# AI_XiaoZhi_WIFI.net
KiCad netlist of a schematic drawn in Altium Designer
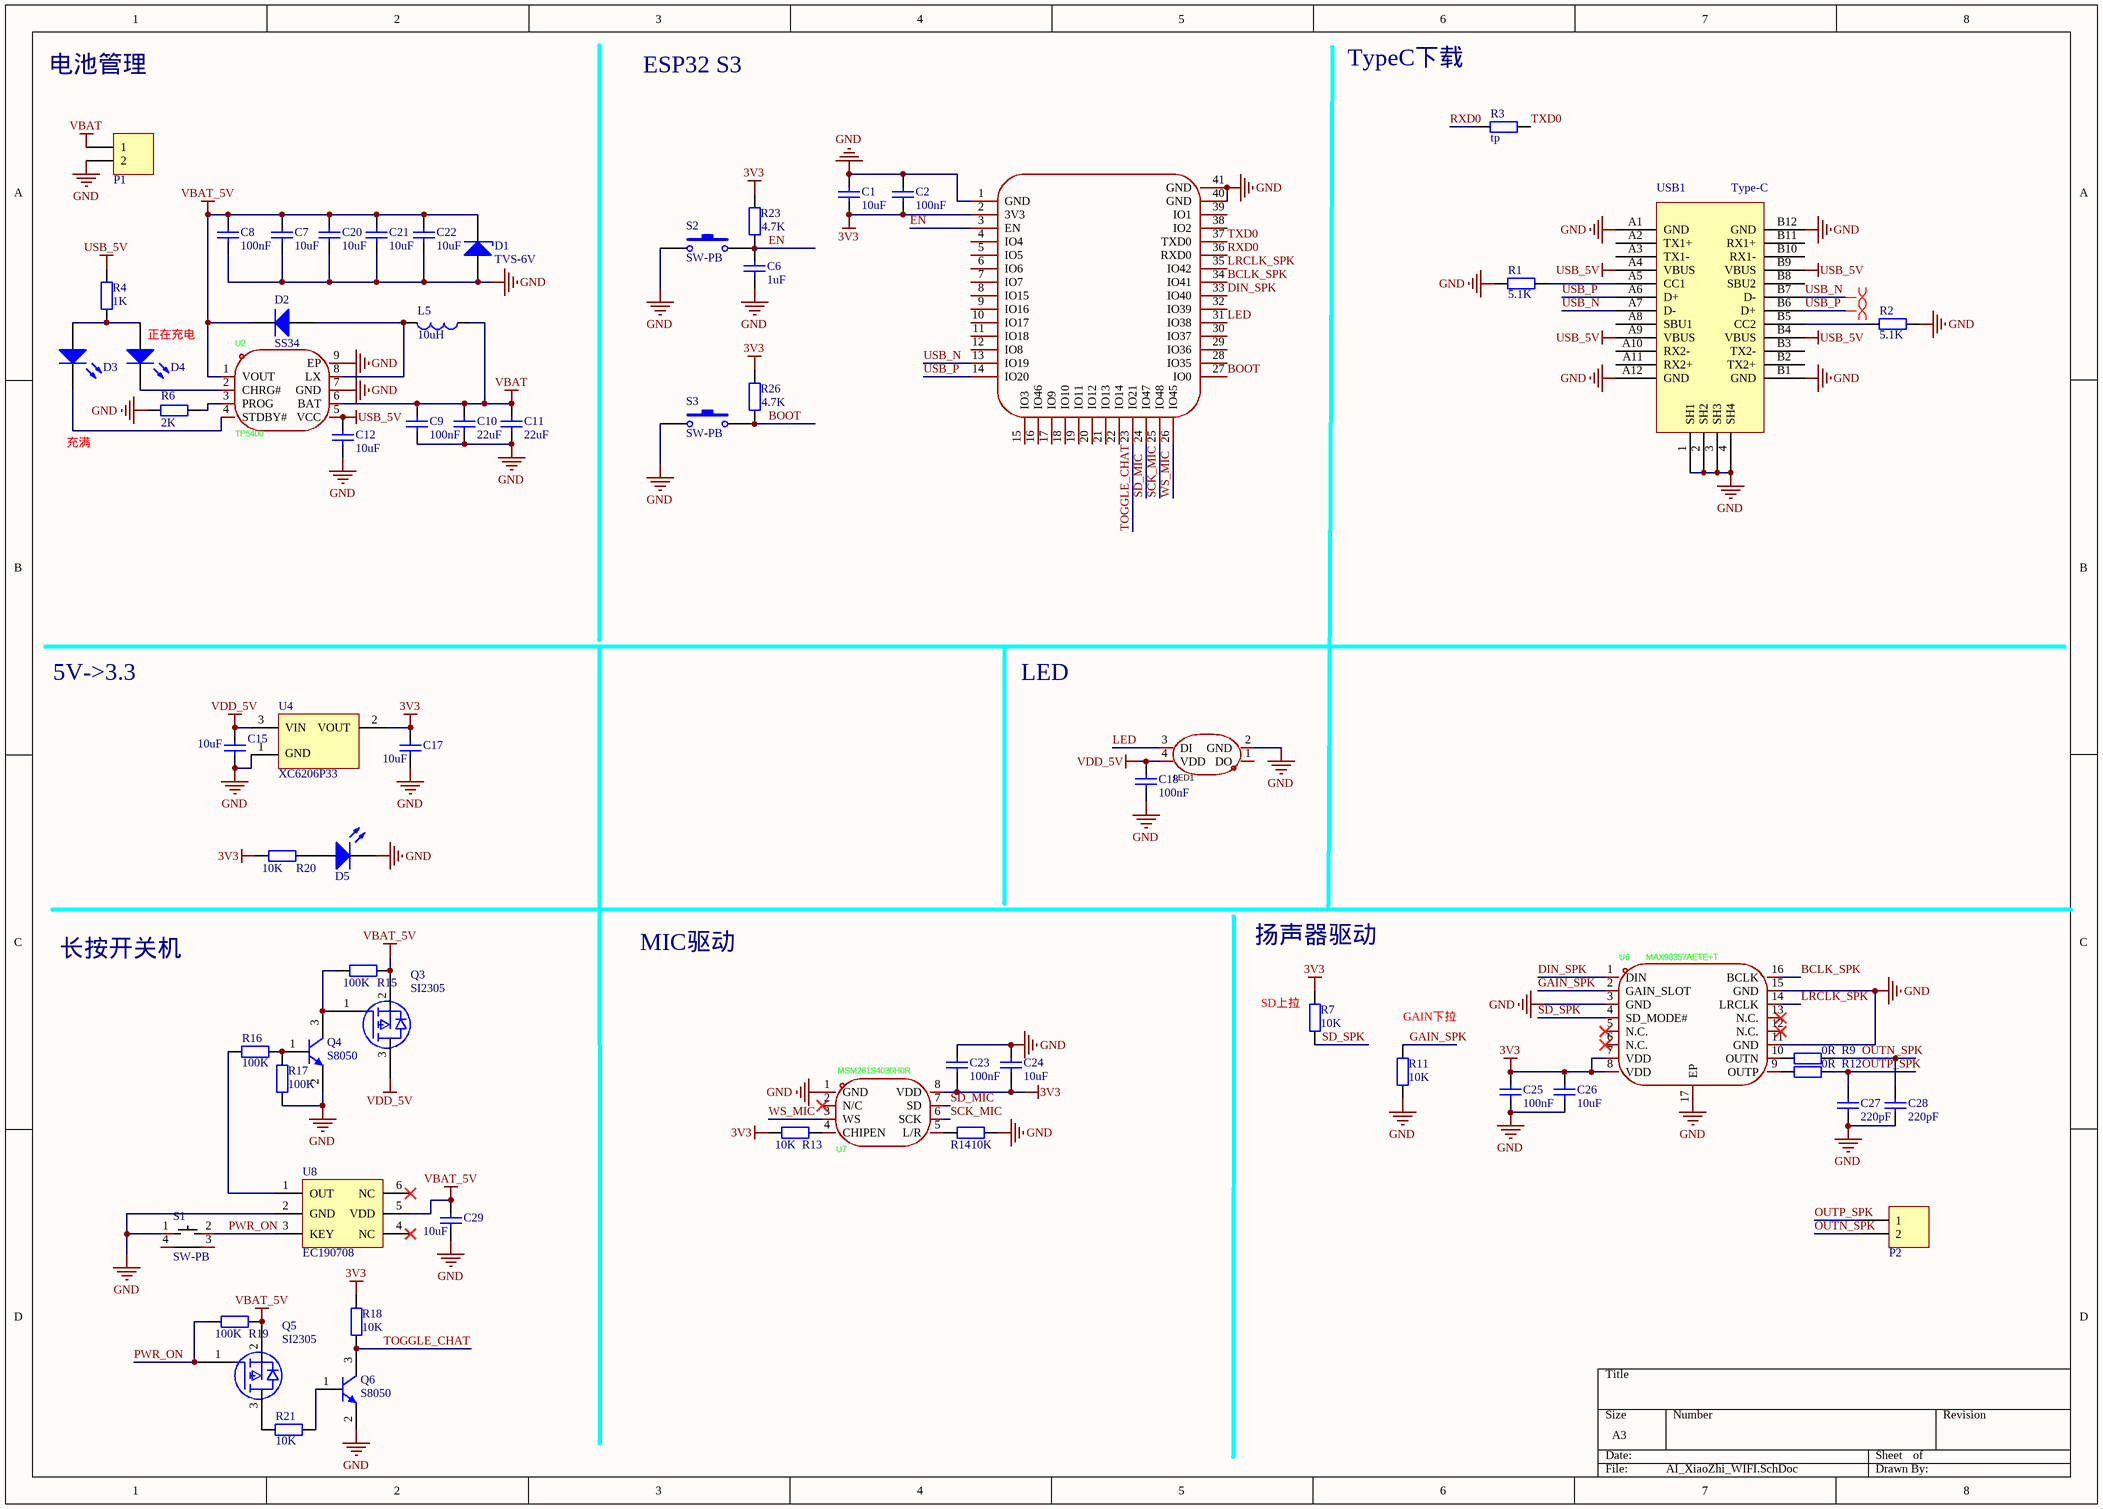
[diagram p0: AI_XiaoZhi_WIFI.SchDoc]

(export (version "E")
  (design (tool "Eeschema 10.0.6"))
  (components
    (comp (ref "C1")
      (value "10uF")
      (footprint "PCBPcblib_MXJ:0603-C")
      (description "无极性电容")
      (fields (field (name "Comment") "CAP") (field (name "PUBLISHER") "Altium Limited"))
      (libsource (lib "PCBSchlib_MXJ") (part "CAP"))
    )
    (comp (ref "C2")
      (value "100nF")
      (footprint "PCBPcblib_MXJ:0603-C")
      (description "无极性电容")
      (fields (field (name "Comment") "CAP") (field (name "PUBLISHER") "Altium Limited"))
      (libsource (lib "PCBSchlib_MXJ") (part "CAP"))
    )
    (comp (ref "C6")
      (value "1uF")
      (footprint "PCBPcblib_MXJ:0603-C")
      (description "无极性电容")
      (fields (field (name "Comment") "CAP") (field (name "PUBLISHER") "Altium Limited"))
      (libsource (lib "PCBSchlib_MXJ") (part "CAP"))
    )
    (comp (ref "C7")
      (value "10uF")
      (footprint "PCBPcblib_MXJ:0603-C")
      (description "无极性电容")
      (fields (field (name "Comment") "CAP") (field (name "PUBLISHER") "Altium Limited"))
      (libsource (lib "PCBSchlib_MXJ") (part "CAP"))
    )
    (comp (ref "C8")
      (value "100nF")
      (footprint "PCBPcblib_MXJ:0603-C")
      (description "无极性电容")
      (fields (field (name "Comment") "CAP") (field (name "PUBLISHER") "Altium Limited"))
      (libsource (lib "PCBSchlib_MXJ") (part "CAP"))
    )
    (comp (ref "C9")
      (value "100nF")
      (footprint "PCBPcblib_MXJ:0603-C")
      (description "无极性电容")
      (fields (field (name "Comment") "CAP") (field (name "PUBLISHER") "Altium Limited"))
      (libsource (lib "PCBSchlib_MXJ") (part "CAP"))
    )
    (comp (ref "C10")
      (value "22uF")
      (footprint "PCBPcblib_MXJ:0603-C")
      (description "无极性电容")
      (fields (field (name "Comment") "CAP") (field (name "PUBLISHER") "Altium Limited"))
      (libsource (lib "PCBSchlib_MXJ") (part "CAP"))
    )
    (comp (ref "C11")
      (value "22uF")
      (footprint "PCBPcblib_MXJ:0603-C")
      (description "无极性电容")
      (fields (field (name "Comment") "CAP") (field (name "PUBLISHER") "Altium Limited"))
      (libsource (lib "PCBSchlib_MXJ") (part "CAP"))
    )
    (comp (ref "C12")
      (value "10uF")
      (footprint "PCBPcblib_MXJ:0603-C")
      (description "无极性电容")
      (fields (field (name "Comment") "CAP") (field (name "PUBLISHER") "Altium Limited"))
      (libsource (lib "PCBSchlib_MXJ") (part "CAP"))
    )
    (comp (ref "C15")
      (value "10uF")
      (footprint "PCBPcblib_MXJ:0603-C")
      (description "无极性电容")
      (fields (field (name "Comment") "CAP") (field (name "PUBLISHER") "Altium Limited"))
      (libsource (lib "PCBSchlib_MXJ") (part "CAP"))
    )
    (comp (ref "C17")
      (value "10uF")
      (footprint "PCBPcblib_MXJ:0603-C")
      (description "无极性电容")
      (fields (field (name "Comment") "CAP") (field (name "PUBLISHER") "Altium Limited"))
      (libsource (lib "PCBSchlib_MXJ") (part "CAP"))
    )
    (comp (ref "C18")
      (value "100nF")
      (footprint "PCBPcblib_MXJ:0603-C")
      (description "无极性电容")
      (fields (field (name "Comment") "CAP") (field (name "PUBLISHER") "Altium Limited"))
      (libsource (lib "PCBSchlib_MXJ") (part "CAP"))
    )
    (comp (ref "C20")
      (value "10uF")
      (footprint "PCBPcblib_MXJ:0603-C")
      (description "无极性电容")
      (fields (field (name "Comment") "CAP") (field (name "PUBLISHER") "Altium Limited"))
      (libsource (lib "PCBSchlib_MXJ") (part "CAP"))
    )
    (comp (ref "C21")
      (value "10uF")
      (footprint "PCBPcblib_MXJ:0603-C")
      (description "无极性电容")
      (fields (field (name "Comment") "CAP") (field (name "PUBLISHER") "Altium Limited"))
      (libsource (lib "PCBSchlib_MXJ") (part "CAP"))
    )
    (comp (ref "C22")
      (value "10uF")
      (footprint "PCBPcblib_MXJ:0603-C")
      (description "无极性电容")
      (fields (field (name "Comment") "CAP") (field (name "PUBLISHER") "Altium Limited"))
      (libsource (lib "PCBSchlib_MXJ") (part "CAP"))
    )
    (comp (ref "C23")
      (value "100nF")
      (footprint "PCBPcblib_MXJ:0603-C")
      (description "无极性电容")
      (fields (field (name "Comment") "CAP") (field (name "PUBLISHER") "Altium Limited"))
      (libsource (lib "PCBSchlib_MXJ") (part "CAP"))
    )
    (comp (ref "C24")
      (value "10uF")
      (footprint "PCBPcblib_MXJ:0603-C")
      (description "无极性电容")
      (fields (field (name "Comment") "CAP") (field (name "PUBLISHER") "Altium Limited"))
      (libsource (lib "PCBSchlib_MXJ") (part "CAP"))
    )
    (comp (ref "C25")
      (value "100nF")
      (footprint "PCBPcblib_MXJ:0603-C")
      (description "无极性电容")
      (fields (field (name "Comment") "CAP") (field (name "PUBLISHER") "Altium Limited"))
      (libsource (lib "PCBSchlib_MXJ") (part "CAP"))
    )
    (comp (ref "C26")
      (value "10uF")
      (footprint "PCBPcblib_MXJ:0603-C")
      (description "无极性电容")
      (fields (field (name "Comment") "CAP") (field (name "PUBLISHER") "Altium Limited"))
      (libsource (lib "PCBSchlib_MXJ") (part "CAP"))
    )
    (comp (ref "C27")
      (value "220pF")
      (footprint "PCBPcblib_MXJ:0603-C")
      (description "无极性电容")
      (fields (field (name "Comment") "CAP") (field (name "PUBLISHER") "Altium Limited"))
      (libsource (lib "PCBSchlib_MXJ") (part "CAP"))
    )
    (comp (ref "C28")
      (value "220pF")
      (footprint "PCBPcblib_MXJ:0603-C")
      (description "无极性电容")
      (fields (field (name "Comment") "CAP") (field (name "PUBLISHER") "Altium Limited"))
      (libsource (lib "PCBSchlib_MXJ") (part "CAP"))
    )
    (comp (ref "C29")
      (value "10uF")
      (footprint "PCBPcblib_MXJ:0603-C")
      (description "无极性电容")
      (fields (field (name "Comment") "CAP") (field (name "PUBLISHER") "Altium Limited"))
      (libsource (lib "PCBSchlib_MXJ") (part "CAP"))
    )
    (comp (ref "D1")
      (value "TVS-6V")
      (footprint "PCBPcblib_MXJ:DIODE-SMA")
      (description "稳压二极管")
      (fields (field (name "Comment") "Diode-Z") (field (name "PUBLISHER") "Altium Limited"))
      (libsource (lib "PCBSchlib_MXJ") (part "Diode-Z"))
    )
    (comp (ref "D2")
      (value "Diode")
      (footprint "DIODE-SMA")
      (description "二极管")
      (fields (field (name "TYPE") "SS34") (field (name "PUBLISHER") "Altium Limited"))
      (libsource (lib "PCBSchlib_MXJ") (part "Diode"))
    )
    (comp (ref "D3")
      (value "LED")
      (footprint "PCBPcblib_MXJ:0603-LED")
      (description "发光二极管")
      (fields (field (name "PUBLISHER") "Altium Limited"))
      (libsource (lib "PCBSchlib_MXJ") (part "LED"))
    )
    (comp (ref "D4")
      (value "LED")
      (footprint "PCBPcblib_MXJ:0603-LED")
      (description "发光二极管")
      (fields (field (name "PUBLISHER") "Altium Limited"))
      (libsource (lib "PCBSchlib_MXJ") (part "LED"))
    )
    (comp (ref "D5")
      (value "LED")
      (footprint "PCBPcblib_MXJ:0603-LED")
      (description "发光二极管")
      (fields (field (name "PUBLISHER") "Altium Limited"))
      (libsource (lib "PCBSchlib_MXJ") (part "LED"))
    )
    (comp (ref "L5")
      (value "10uH")
      (footprint "PCBPcblib_MXJ:SMD_L4.4-W4.2")
      (description "电感")
      (fields (field (name "Comment") "Inductor") (field (name "PUBLISHER") "Altium Limited"))
      (libsource (lib "PCBSchlib_MXJ") (part "Inductor"))
    )
    (comp (ref "LED1")
      (value "XL-2020RGBC-WS2812B")
      (footprint "LED-SMD_4P-L2.0-W2.0-BR-1")
      (fields (field (name "MANUFACTURER") "XINGLIGHT(成兴光)"))
      (libsource (lib "PCBSchlib_MXJ") (part "XL-2020RGBC-WS2812B"))
    )
    (comp (ref "P1")
      (value "Header 2")
      (footprint "PCBPcblib_MXJ:CONN-SMD_2P-P1.25-HC-1.25-2PWT")
      (description "接插件")
      (fields (field (name "PUBLISHER") "Altium Limited"))
      (libsource (lib "PCBSchlib_MXJ") (part "Header 2"))
    )
    (comp (ref "P2")
      (value "Header 2")
      (footprint "PCBPcblib_MXJ:CONN-SMD_2P-P1.25-HC-1.25-2PWT")
      (description "接插件")
      (fields (field (name "PUBLISHER") "Altium Limited"))
      (libsource (lib "PCBSchlib_MXJ") (part "Header 2"))
    )
    (comp (ref "Q3")
      (value "SI2305")
      (footprint "SOT-23")
      (description "PNP MOS管")
      (fields (field (name "Comment") "PMOS") (field (name "PUBLISHER") "Altium Limited"))
      (libsource (lib "PCBSchlib_MXJ") (part "PMOS"))
    )
    (comp (ref "Q4")
      (value "S8050")
      (footprint "PCBPcblib_MXJ:SOT-23")
      (description "NPN三极管")
      (fields (field (name "PUBLISHER") "Altium Limited"))
      (libsource (lib "PCBSchlib_MXJ") (part "NPN_BJT"))
    )
    (comp (ref "Q5")
      (value "SI2305")
      (footprint "SOT-23")
      (description "PNP MOS管")
      (fields (field (name "Comment") "PMOS") (field (name "PUBLISHER") "Altium Limited"))
      (libsource (lib "PCBSchlib_MXJ") (part "PMOS"))
    )
    (comp (ref "Q6")
      (value "S8050")
      (footprint "PCBPcblib_MXJ:SOT-23")
      (description "NPN三极管")
      (fields (field (name "PUBLISHER") "Altium Limited"))
      (libsource (lib "PCBSchlib_MXJ") (part "NPN_BJT"))
    )
    (comp (ref "R1")
      (value "5.1K")
      (footprint "PCBPcblib_MXJ:0603-R")
      (description "贴片电阻")
      (fields (field (name "Comment") "RES") (field (name "PUBLISHER") "Altium Limited"))
      (libsource (lib "") (part "RES_2"))
    )
    (comp (ref "R2")
      (value "5.1K")
      (footprint "PCBPcblib_MXJ:0603-R")
      (description "贴片电阻")
      (fields (field (name "Comment") "RES") (field (name "PUBLISHER") "Altium Limited"))
      (libsource (lib "") (part "RES_2"))
    )
    (comp (ref "R3")
      (value "tp")
      (footprint "PCBPcblib_MXJ:0603-R")
      (description "贴片电阻")
      (fields (field (name "Comment") "RES") (field (name "PUBLISHER") "Altium Limited"))
      (libsource (lib "") (part "RES_1"))
    )
    (comp (ref "R4")
      (value "1K")
      (footprint "PCBPcblib_MXJ:0603-R")
      (description "贴片电阻")
      (fields (field (name "Comment") "RES") (field (name "PUBLISHER") "Altium Limited"))
      (libsource (lib "PCBSchlib_MXJ") (part "RES"))
    )
    (comp (ref "R6")
      (value "2K")
      (footprint "PCBPcblib_MXJ:0603-R")
      (description "贴片电阻")
      (fields (field (name "Comment") "RES") (field (name "PUBLISHER") "Altium Limited"))
      (libsource (lib "") (part "RES_2"))
    )
    (comp (ref "R7")
      (value "10K")
      (footprint "PCBPcblib_MXJ:0603-R")
      (description "贴片电阻")
      (fields (field (name "Comment") "RES") (field (name "PUBLISHER") "Altium Limited"))
      (libsource (lib "PCBSchlib_MXJ") (part "RES"))
    )
    (comp (ref "R9")
      (value "0R")
      (footprint "PCBPcblib_MXJ:0603-R")
      (description "贴片电阻")
      (fields (field (name "Comment") "RES") (field (name "PUBLISHER") "Altium Limited"))
      (libsource (lib "") (part "RES_1"))
    )
    (comp (ref "R11")
      (value "10K")
      (footprint "PCBPcblib_MXJ:0603-R")
      (description "贴片电阻")
      (fields (field (name "Comment") "RES") (field (name "PUBLISHER") "Altium Limited"))
      (libsource (lib "PCBSchlib_MXJ") (part "RES"))
    )
    (comp (ref "R12")
      (value "0R")
      (footprint "PCBPcblib_MXJ:0603-R")
      (description "贴片电阻")
      (fields (field (name "Comment") "RES") (field (name "PUBLISHER") "Altium Limited"))
      (libsource (lib "") (part "RES_1"))
    )
    (comp (ref "R13")
      (value "10K")
      (footprint "PCBPcblib_MXJ:0603-R")
      (description "贴片电阻")
      (fields (field (name "Comment") "RES") (field (name "PUBLISHER") "Altium Limited"))
      (libsource (lib "") (part "RES_2"))
    )
    (comp (ref "R14")
      (value "10K")
      (footprint "PCBPcblib_MXJ:0603-R")
      (description "贴片电阻")
      (fields (field (name "Comment") "RES") (field (name "PUBLISHER") "Altium Limited"))
      (libsource (lib "") (part "RES_1"))
    )
    (comp (ref "R15")
      (value "100K")
      (footprint "PCBPcblib_MXJ:0603-R")
      (description "贴片电阻")
      (fields (field (name "Comment") "RES") (field (name "PUBLISHER") "Altium Limited"))
      (libsource (lib "") (part "RES_2"))
    )
    (comp (ref "R16")
      (value "100K")
      (footprint "PCBPcblib_MXJ:0603-R")
      (description "贴片电阻")
      (fields (field (name "Comment") "RES") (field (name "PUBLISHER") "Altium Limited"))
      (libsource (lib "") (part "RES_1"))
    )
    (comp (ref "R17")
      (value "100K")
      (footprint "PCBPcblib_MXJ:0603-R")
      (description "贴片电阻")
      (fields (field (name "Comment") "RES") (field (name "PUBLISHER") "Altium Limited"))
      (libsource (lib "") (part "RES_3"))
    )
    (comp (ref "R18")
      (value "10K")
      (footprint "PCBPcblib_MXJ:0603-R")
      (description "贴片电阻")
      (fields (field (name "Comment") "RES") (field (name "PUBLISHER") "Altium Limited"))
      (libsource (lib "") (part "RES_3"))
    )
    (comp (ref "R19")
      (value "100K")
      (footprint "PCBPcblib_MXJ:0603-R")
      (description "贴片电阻")
      (fields (field (name "Comment") "RES") (field (name "PUBLISHER") "Altium Limited"))
      (libsource (lib "") (part "RES_2"))
    )
    (comp (ref "R20")
      (value "10K")
      (footprint "PCBPcblib_MXJ:0603-R")
      (description "贴片电阻")
      (fields (field (name "Comment") "RES") (field (name "PUBLISHER") "Altium Limited"))
      (libsource (lib "") (part "RES_2"))
    )
    (comp (ref "R21")
      (value "10K")
      (footprint "PCBPcblib_MXJ:0603-R")
      (description "贴片电阻")
      (fields (field (name "Comment") "RES") (field (name "PUBLISHER") "Altium Limited"))
      (libsource (lib "") (part "RES_1"))
    )
    (comp (ref "R23")
      (value "4.7K")
      (footprint "PCBPcblib_MXJ:0603-R")
      (description "贴片电阻")
      (fields (field (name "Comment") "RES") (field (name "PUBLISHER") "Altium Limited"))
      (libsource (lib "PCBSchlib_MXJ") (part "RES"))
    )
    (comp (ref "R26")
      (value "4.7K")
      (footprint "PCBPcblib_MXJ:0603-R")
      (description "贴片电阻")
      (fields (field (name "Comment") "RES") (field (name "PUBLISHER") "Altium Limited"))
      (libsource (lib "PCBSchlib_MXJ") (part "RES"))
    )
    (comp (ref "S1")
      (value "SW-PB")
      (footprint "PCBPcblib_MXJ:SW_TS")
      (description "微动开关")
      (fields (field (name "PUBLISHER") "Altium Limited"))
      (libsource (lib "PCBSchlib_MXJ") (part "SW-TS"))
    )
    (comp (ref "S2")
      (value "SW-PB")
      (footprint "PCBPcblib_MXJ:SW-SMD_L3.9-W3.0-P4.45")
      (description "微动开关")
      (fields (field (name "PUBLISHER") "Altium Limited"))
      (libsource (lib "PCBSchlib_MXJ") (part "SW-PB"))
    )
    (comp (ref "S3")
      (value "SW-PB")
      (footprint "PCBPcblib_MXJ:SW-SMD_L3.9-W3.0-P4.45")
      (description "微动开关")
      (fields (field (name "PUBLISHER") "Altium Limited"))
      (libsource (lib "PCBSchlib_MXJ") (part "SW-PB"))
    )
    (comp (ref "U2")
      (value "TP5400")
      (footprint "ESOP-8")
      (description "单节锂电池充电管理模块")
      (fields (field (name "MANUFACTURER") "TOPPOWER(南京拓微)"))
      (libsource (lib "PCBSchlib_MXJ") (part "TP5400"))
    )
    (comp (ref "U3")
      (value "ESP32-S3-WROOM-1U-N16R8")
      (footprint "PCBPcblib_MXJ:WIRELM-SMD_ESP32-S3-WROOM-1")
      (fields (field (name "MANUFACTURER") "ESPRESSIF(乐鑫)"))
      (libsource (lib "PCBSchlib_MXJ") (part "ESP32-S3-WROOM-1U-N16R8"))
    )
    (comp (ref "U4")
      (value "XC6206P33")
      (footprint "SOT-23")
      (description "LDO稳压芯片")
      (libsource (lib "PCBSchlib_MXJ") (part "XC6206PXXX"))
    )
    (comp (ref "U6")
      (value "MAX98357AETE+T")
      (footprint "TQFN-16")
      (description "扬声器驱动芯片")
      (fields (field (name "MANUFACTURER") "ADI(亚德诺)/MAXIM(美信)"))
      (libsource (lib "PCBSchlib_MXJ") (part "MAX98357AETE+T"))
    )
    (comp (ref "U7")
      (value "MSM261S4030H0R")
      (footprint "MIC-SMD_8P-L4.0-W3.0-P1.00-BR")
      (fields (field (name "MANUFACTURER") "MEMS(敏芯微)"))
      (libsource (lib "PCBSchlib_MXJ") (part "MIC"))
    )
    (comp (ref "U8")
      (value "EC190708")
      (footprint "PCBPcblib_MXJ:SOT-23-6")
      (description "长按开关机")
      (libsource (lib "PCBSchlib_MXJ") (part "EC190708"))
    )
    (comp (ref "USB1")
      (value "Type-C")
      (footprint "Type-C-TOP")
      (description "16Pins TYPEC")
      (libsource (lib "PCBSchlib_MXJ") (part "USB-Type-C-TOP"))
    )
  )
  (nets
    (net (code "1") (name "/BCLK_SPK") (class "Default")
      (node (ref "U3") (pin "34") (pinfunction "IO41_34") (pintype "passive"))
      (node (ref "U6") (pin "16") (pinfunction "BCLK_16") (pintype "passive"))
    )
    (net (code "2") (name "/BOOT") (class "Default")
      (node (ref "R26") (pin "1") (pinfunction "1_1") (pintype "passive"))
      (node (ref "S3") (pin "2") (pinfunction "2_2") (pintype "passive"))
      (node (ref "U3") (pin "27") (pinfunction "IO0_27") (pintype "passive"))
    )
    (net (code "3") (name "/DIN_SPK") (class "Default")
      (node (ref "U3") (pin "33") (pinfunction "IO40_33") (pintype "passive"))
      (node (ref "U6") (pin "1") (pinfunction "DIN_1") (pintype "passive"))
    )
    (net (code "4") (name "/EN") (class "Default")
      (node (ref "C6") (pin "1") (pinfunction "1_1") (pintype "passive"))
      (node (ref "R23") (pin "1") (pinfunction "1_1") (pintype "passive"))
      (node (ref "S2") (pin "2") (pinfunction "2_2") (pintype "passive"))
      (node (ref "U3") (pin "3") (pinfunction "EN_3") (pintype "passive"))
    )
    (net (code "5") (name "/GAIN_SPK") (class "Default")
      (node (ref "R11") (pin "2") (pinfunction "2_2") (pintype "passive"))
      (node (ref "U6") (pin "2") (pinfunction "GAIN_SLOT_2") (pintype "passive"))
    )
    (net (code "6") (name "/LED") (class "Default")
      (node (ref "LED1") (pin "3") (pinfunction "DI_3") (pintype "passive"))
      (node (ref "U3") (pin "31") (pinfunction "IO38_31") (pintype "passive"))
    )
    (net (code "7") (name "/LRCLK_SPK") (class "Default")
      (node (ref "U3") (pin "35") (pinfunction "IO42_35") (pintype "passive"))
      (node (ref "U6") (pin "14") (pinfunction "LRCLK_14") (pintype "passive"))
    )
    (net (code "8") (name "/OUTN_SPK") (class "Default")
      (node (ref "C28") (pin "1") (pinfunction "1_1") (pintype "passive"))
      (node (ref "P2") (pin "2") (pinfunction "2_2") (pintype "passive"))
      (node (ref "R9") (pin "2") (pinfunction "2_2") (pintype "passive"))
    )
    (net (code "9") (name "/OUTP_SPK") (class "Default")
      (node (ref "C27") (pin "1") (pinfunction "1_1") (pintype "passive"))
      (node (ref "P2") (pin "1") (pinfunction "1_1") (pintype "passive"))
      (node (ref "R12") (pin "2") (pinfunction "2_2") (pintype "passive"))
    )
    (net (code "10") (name "/PWR_ON") (class "Default")
      (node (ref "Q5") (pin "1") (pinfunction "G_1") (pintype "passive"))
      (node (ref "R19") (pin "2") (pinfunction "2_2") (pintype "passive"))
      (node (ref "S1") (pin "2") (pinfunction "2_2") (pintype "passive"))
      (node (ref "U8") (pin "3") (pinfunction "KEY_3") (pintype "passive"))
    )
    (net (code "11") (name "/RXD0") (class "Default")
      (node (ref "R3") (pin "1") (pinfunction "1_1") (pintype "passive"))
      (node (ref "U3") (pin "36") (pinfunction "RXD0_36") (pintype "passive"))
    )
    (net (code "12") (name "/SCK_MIC") (class "Default")
      (node (ref "U3") (pin "25") (pinfunction "IO48_25") (pintype "passive"))
      (node (ref "U7") (pin "6") (pinfunction "SCK_6") (pintype "passive"))
    )
    (net (code "13") (name "/SD_MIC") (class "Default")
      (node (ref "U3") (pin "24") (pinfunction "IO47_24") (pintype "passive"))
      (node (ref "U7") (pin "7") (pinfunction "SD_7") (pintype "passive"))
    )
    (net (code "14") (name "/SD_SPK") (class "Default")
      (node (ref "R7") (pin "1") (pinfunction "1_1") (pintype "passive"))
      (node (ref "U6") (pin "4") (pinfunction "SD_MODE#_4") (pintype "passive"))
    )
    (net (code "15") (name "/TOGGLE_CHAT") (class "Default")
      (node (ref "Q6") (pin "3") (pinfunction "C_3") (pintype "passive"))
      (node (ref "R18") (pin "2") (pinfunction "2_2") (pintype "passive"))
      (node (ref "U3") (pin "23") (pinfunction "IO21_23") (pintype "passive"))
    )
    (net (code "16") (name "/TXD0") (class "Default")
      (node (ref "R3") (pin "2") (pinfunction "2_2") (pintype "passive"))
      (node (ref "U3") (pin "37") (pinfunction "TXD0_37") (pintype "passive"))
    )
    (net (code "17") (name "/USB_N") (class "Default")
      (node (ref "U3") (pin "13") (pinfunction "IO19_13") (pintype "passive"))
      (node (ref "USB1") (pin "A7") (pinfunction "D-_A7") (pintype "passive"))
      (node (ref "USB1") (pin "B7") (pinfunction "D-_B7") (pintype "passive"))
    )
    (net (code "18") (name "/USB_P") (class "Default")
      (node (ref "U3") (pin "14") (pinfunction "IO20_14") (pintype "passive"))
      (node (ref "USB1") (pin "A6") (pinfunction "D+_A6") (pintype "passive"))
      (node (ref "USB1") (pin "B6") (pinfunction "D+_B6") (pintype "passive"))
    )
    (net (code "19") (name "/WS_MIC") (class "Default")
      (node (ref "U3") (pin "26") (pinfunction "IO45_26") (pintype "passive"))
      (node (ref "U7") (pin "3") (pinfunction "WS_3") (pintype "passive"))
    )
    (net (code "20") (name "3V3") (class "Default")
      (node (ref "C1") (pin "2") (pinfunction "2_2") (pintype "passive"))
      (node (ref "C17") (pin "2") (pinfunction "2_2") (pintype "passive"))
      (node (ref "C2") (pin "2") (pinfunction "2_2") (pintype "passive"))
      (node (ref "C23") (pin "1") (pinfunction "1_1") (pintype "passive"))
      (node (ref "C24") (pin "1") (pinfunction "1_1") (pintype "passive"))
      (node (ref "C25") (pin "1") (pinfunction "1_1") (pintype "passive"))
      (node (ref "C26") (pin "1") (pinfunction "1_1") (pintype "passive"))
      (node (ref "R13") (pin "2") (pinfunction "2_2") (pintype "passive"))
      (node (ref "R18") (pin "1") (pinfunction "1_1") (pintype "passive"))
      (node (ref "R20") (pin "2") (pinfunction "2_2") (pintype "passive"))
      (node (ref "R23") (pin "2") (pinfunction "2_2") (pintype "passive"))
      (node (ref "R26") (pin "2") (pinfunction "2_2") (pintype "passive"))
      (node (ref "R7") (pin "2") (pinfunction "2_2") (pintype "passive"))
      (node (ref "U3") (pin "2") (pinfunction "3V3_2") (pintype "passive"))
      (node (ref "U4") (pin "2") (pinfunction "VOUT_2") (pintype "passive"))
      (node (ref "U6") (pin "7") (pinfunction "VDD_7") (pintype "passive"))
      (node (ref "U6") (pin "8") (pinfunction "VDD_8") (pintype "passive"))
      (node (ref "U7") (pin "8") (pinfunction "VDD_8") (pintype "passive"))
    )
    (net (code "21") (name "GND") (class "Default")
      (node (ref "C1") (pin "1") (pinfunction "1_1") (pintype "passive"))
      (node (ref "C10") (pin "2") (pinfunction "2_2") (pintype "passive"))
      (node (ref "C11") (pin "2") (pinfunction "2_2") (pintype "passive"))
      (node (ref "C12") (pin "2") (pinfunction "2_2") (pintype "passive"))
      (node (ref "C15") (pin "1") (pinfunction "1_1") (pintype "passive"))
      (node (ref "C17") (pin "1") (pinfunction "1_1") (pintype "passive"))
      (node (ref "C18") (pin "1") (pinfunction "1_1") (pintype "passive"))
      (node (ref "C2") (pin "1") (pinfunction "1_1") (pintype "passive"))
      (node (ref "C20") (pin "2") (pinfunction "2_2") (pintype "passive"))
      (node (ref "C21") (pin "2") (pinfunction "2_2") (pintype "passive"))
      (node (ref "C22") (pin "2") (pinfunction "2_2") (pintype "passive"))
      (node (ref "C23") (pin "2") (pinfunction "2_2") (pintype "passive"))
      (node (ref "C24") (pin "2") (pinfunction "2_2") (pintype "passive"))
      (node (ref "C25") (pin "2") (pinfunction "2_2") (pintype "passive"))
      (node (ref "C26") (pin "2") (pinfunction "2_2") (pintype "passive"))
      (node (ref "C27") (pin "2") (pinfunction "2_2") (pintype "passive"))
      (node (ref "C28") (pin "2") (pinfunction "2_2") (pintype "passive"))
      (node (ref "C29") (pin "1") (pinfunction "1_1") (pintype "passive"))
      (node (ref "C6") (pin "2") (pinfunction "2_2") (pintype "passive"))
      (node (ref "C7") (pin "2") (pinfunction "2_2") (pintype "passive"))
      (node (ref "C8") (pin "2") (pinfunction "2_2") (pintype "passive"))
      (node (ref "C9") (pin "2") (pinfunction "2_2") (pintype "passive"))
      (node (ref "D1") (pin "1") (pinfunction "A_1") (pintype "passive"))
      (node (ref "D5") (pin "2") (pinfunction "K_2") (pintype "passive"))
      (node (ref "LED1") (pin "2") (pinfunction "GND_2") (pintype "passive"))
      (node (ref "P1") (pin "2") (pinfunction "2_2") (pintype "passive"))
      (node (ref "Q4") (pin "2") (pinfunction "E_2") (pintype "passive"))
      (node (ref "Q6") (pin "2") (pinfunction "E_2") (pintype "passive"))
      (node (ref "R1") (pin "2") (pinfunction "2_2") (pintype "passive"))
      (node (ref "R11") (pin "1") (pinfunction "1_1") (pintype "passive"))
      (node (ref "R14") (pin "2") (pinfunction "2_2") (pintype "passive"))
      (node (ref "R17") (pin "2") (pinfunction "2_2") (pintype "passive"))
      (node (ref "R2") (pin "1") (pinfunction "1_1") (pintype "passive"))
      (node (ref "R6") (pin "2") (pinfunction "2_2") (pintype "passive"))
      (node (ref "S1") (pin "1") (pinfunction "1_1") (pintype "passive"))
      (node (ref "S2") (pin "1") (pinfunction "1_1") (pintype "passive"))
      (node (ref "S3") (pin "1") (pinfunction "1_1") (pintype "passive"))
      (node (ref "U2") (pin "7") (pinfunction "GND_7") (pintype "passive"))
      (node (ref "U2") (pin "9") (pinfunction "EP_9") (pintype "passive"))
      (node (ref "U3") (pin "1") (pinfunction "GND_1") (pintype "passive"))
      (node (ref "U3") (pin "40") (pinfunction "GND_40") (pintype "passive"))
      (node (ref "U3") (pin "41") (pinfunction "GND_41") (pintype "passive"))
      (node (ref "U4") (pin "1") (pinfunction "GND_1") (pintype "passive"))
      (node (ref "U6") (pin "11") (pinfunction "GND_11") (pintype "passive"))
      (node (ref "U6") (pin "15") (pinfunction "GND_15") (pintype "passive"))
      (node (ref "U6") (pin "17") (pinfunction "EP_17") (pintype "passive"))
      (node (ref "U6") (pin "3") (pinfunction "GND_3") (pintype "passive"))
      (node (ref "U7") (pin "1") (pinfunction "GND_1") (pintype "passive"))
      (node (ref "U8") (pin "2") (pinfunction "GND_2") (pintype "passive"))
      (node (ref "USB1") (pin "1") (pinfunction "SH1_1") (pintype "passive"))
      (node (ref "USB1") (pin "2") (pinfunction "SH2_2") (pintype "passive"))
      (node (ref "USB1") (pin "3") (pinfunction "SH3_3") (pintype "passive"))
      (node (ref "USB1") (pin "4") (pinfunction "SH4_4") (pintype "passive"))
      (node (ref "USB1") (pin "A1") (pinfunction "GND_A1") (pintype "passive"))
      (node (ref "USB1") (pin "A12") (pinfunction "GND_A12") (pintype "passive"))
      (node (ref "USB1") (pin "B1") (pinfunction "GND_B1") (pintype "passive"))
      (node (ref "USB1") (pin "B12") (pinfunction "GND_B12") (pintype "passive"))
    )
    (net (code "22") (name "Net-(D2-A)") (class "Default")
      (node (ref "D2") (pin "1") (pinfunction "A_1") (pintype "passive"))
      (node (ref "L5") (pin "2") (pinfunction "2_2") (pintype "passive"))
      (node (ref "U2") (pin "8") (pinfunction "LX_8") (pintype "passive"))
    )
    (net (code "23") (name "Net-(D3-A)") (class "Default")
      (node (ref "D3") (pin "1") (pinfunction "A_1") (pintype "passive"))
      (node (ref "D4") (pin "1") (pinfunction "A_1") (pintype "passive"))
      (node (ref "R4") (pin "1") (pinfunction "1_1") (pintype "passive"))
    )
    (net (code "24") (name "Net-(D3-K)") (class "Default")
      (node (ref "D3") (pin "2") (pinfunction "K_2") (pintype "passive"))
      (node (ref "U2") (pin "4") (pinfunction "STDBY#_4") (pintype "passive"))
    )
    (net (code "25") (name "Net-(D4-K)") (class "Default")
      (node (ref "D4") (pin "2") (pinfunction "K_2") (pintype "passive"))
      (node (ref "U2") (pin "2") (pinfunction "CHRG#_2") (pintype "passive"))
    )
    (net (code "26") (name "Net-(D5-A)") (class "Default")
      (node (ref "D5") (pin "1") (pinfunction "A_1") (pintype "passive"))
      (node (ref "R20") (pin "1") (pinfunction "1_1") (pintype "passive"))
    )
    (net (code "27") (name "Net-(Q3-G)") (class "Default")
      (node (ref "Q3") (pin "1") (pinfunction "G_1") (pintype "passive"))
      (node (ref "Q4") (pin "3") (pinfunction "C_3") (pintype "passive"))
      (node (ref "R15") (pin "2") (pinfunction "2_2") (pintype "passive"))
    )
    (net (code "28") (name "Net-(Q4-B)") (class "Default")
      (node (ref "Q4") (pin "1") (pinfunction "B_1") (pintype "passive"))
      (node (ref "R16") (pin "2") (pinfunction "2_2") (pintype "passive"))
      (node (ref "R17") (pin "1") (pinfunction "1_1") (pintype "passive"))
    )
    (net (code "29") (name "Net-(Q5-D)") (class "Default")
      (node (ref "Q5") (pin "3") (pinfunction "D_3") (pintype "passive"))
      (node (ref "R21") (pin "1") (pinfunction "1_1") (pintype "passive"))
    )
    (net (code "30") (name "Net-(Q6-B)") (class "Default")
      (node (ref "Q6") (pin "1") (pinfunction "B_1") (pintype "passive"))
      (node (ref "R21") (pin "2") (pinfunction "2_2") (pintype "passive"))
    )
    (net (code "31") (name "Net-(U2-PROG)") (class "Default")
      (node (ref "R6") (pin "1") (pinfunction "1_1") (pintype "passive"))
      (node (ref "U2") (pin "3") (pinfunction "PROG_3") (pintype "passive"))
    )
    (net (code "32") (name "Net-(U6-OUTN)") (class "Default")
      (node (ref "R9") (pin "1") (pinfunction "1_1") (pintype "passive"))
      (node (ref "U6") (pin "10") (pinfunction "OUTN_10") (pintype "passive"))
    )
    (net (code "33") (name "Net-(U6-OUTP)") (class "Default")
      (node (ref "R12") (pin "1") (pinfunction "1_1") (pintype "passive"))
      (node (ref "U6") (pin "9") (pinfunction "OUTP_9") (pintype "passive"))
    )
    (net (code "34") (name "Net-(U7-CHIPEN)") (class "Default")
      (node (ref "R13") (pin "1") (pinfunction "1_1") (pintype "passive"))
      (node (ref "U7") (pin "4") (pinfunction "CHIPEN_4") (pintype "passive"))
    )
    (net (code "35") (name "Net-(U7-L{slash}R)") (class "Default")
      (node (ref "R14") (pin "1") (pinfunction "1_1") (pintype "passive"))
      (node (ref "U7") (pin "5") (pinfunction "L/R_5") (pintype "passive"))
    )
    (net (code "36") (name "Net-(U8-OUT)") (class "Default")
      (node (ref "R16") (pin "1") (pinfunction "1_1") (pintype "passive"))
      (node (ref "U8") (pin "1") (pinfunction "OUT_1") (pintype "passive"))
    )
    (net (code "37") (name "Net-(USB1-CC1)") (class "Default")
      (node (ref "R1") (pin "1") (pinfunction "1_1") (pintype "passive"))
      (node (ref "USB1") (pin "A5") (pinfunction "CC1_A5") (pintype "passive"))
    )
    (net (code "38") (name "Net-(USB1-CC2)") (class "Default")
      (node (ref "R2") (pin "2") (pinfunction "2_2") (pintype "passive"))
      (node (ref "USB1") (pin "B5") (pinfunction "CC2_B5") (pintype "passive"))
    )
    (net (code "39") (name "USB_5V") (class "Default")
      (node (ref "C12") (pin "1") (pinfunction "1_1") (pintype "passive"))
      (node (ref "R4") (pin "2") (pinfunction "2_2") (pintype "passive"))
      (node (ref "U2") (pin "5") (pinfunction "VCC_5") (pintype "passive"))
      (node (ref "USB1") (pin "A4") (pinfunction "VBUS_A4") (pintype "passive"))
      (node (ref "USB1") (pin "A9") (pinfunction "VBUS_A9") (pintype "passive"))
      (node (ref "USB1") (pin "B4") (pinfunction "VBUS_B4") (pintype "passive"))
      (node (ref "USB1") (pin "B9") (pinfunction "VBUS_B9") (pintype "passive"))
    )
    (net (code "40") (name "VBAT") (class "Default")
      (node (ref "C10") (pin "1") (pinfunction "1_1") (pintype "passive"))
      (node (ref "C11") (pin "1") (pinfunction "1_1") (pintype "passive"))
      (node (ref "C9") (pin "1") (pinfunction "1_1") (pintype "passive"))
      (node (ref "L5") (pin "1") (pinfunction "1_1") (pintype "passive"))
      (node (ref "P1") (pin "1") (pinfunction "1_1") (pintype "passive"))
      (node (ref "U2") (pin "6") (pinfunction "BAT_6") (pintype "passive"))
    )
    (net (code "41") (name "VBAT_5V") (class "Default")
      (node (ref "C20") (pin "1") (pinfunction "1_1") (pintype "passive"))
      (node (ref "C21") (pin "1") (pinfunction "1_1") (pintype "passive"))
      (node (ref "C22") (pin "1") (pinfunction "1_1") (pintype "passive"))
      (node (ref "C29") (pin "2") (pinfunction "2_2") (pintype "passive"))
      (node (ref "C7") (pin "1") (pinfunction "1_1") (pintype "passive"))
      (node (ref "C8") (pin "1") (pinfunction "1_1") (pintype "passive"))
      (node (ref "D1") (pin "2") (pinfunction "K_2") (pintype "passive"))
      (node (ref "D2") (pin "2") (pinfunction "K_2") (pintype "passive"))
      (node (ref "Q3") (pin "2") (pinfunction "S_2") (pintype "passive"))
      (node (ref "Q5") (pin "2") (pinfunction "S_2") (pintype "passive"))
      (node (ref "R15") (pin "1") (pinfunction "1_1") (pintype "passive"))
      (node (ref "R19") (pin "1") (pinfunction "1_1") (pintype "passive"))
      (node (ref "U2") (pin "1") (pinfunction "VOUT_1") (pintype "passive"))
      (node (ref "U8") (pin "5") (pinfunction "VDD_5") (pintype "passive"))
    )
    (net (code "42") (name "VDD_5V") (class "Default")
      (node (ref "C15") (pin "2") (pinfunction "2_2") (pintype "passive"))
      (node (ref "C18") (pin "2") (pinfunction "2_2") (pintype "passive"))
      (node (ref "LED1") (pin "4") (pinfunction "VDD_4") (pintype "passive"))
      (node (ref "Q3") (pin "3") (pinfunction "D_3") (pintype "passive"))
      (node (ref "U4") (pin "3") (pinfunction "VIN_3") (pintype "passive"))
    )
    (net (code "43") (name "unconnected-(LED1-DO-Pad1)") (class "Default")
      (node (ref "LED1") (pin "1") (pinfunction "DO_1") (pintype "passive"))
    )
    (net (code "44") (name "unconnected-(S1-Pad3)") (class "Default")
      (node (ref "S1") (pin "3") (pinfunction "3_3") (pintype "passive"))
    )
    (net (code "45") (name "unconnected-(S1-Pad4)") (class "Default")
      (node (ref "S1") (pin "4") (pinfunction "4_4") (pintype "passive"))
    )
    (net (code "46") (name "unconnected-(U3-IO1-Pad39)") (class "Default")
      (node (ref "U3") (pin "39") (pinfunction "IO1_39") (pintype "passive"))
    )
    (net (code "47") (name "unconnected-(U3-IO2-Pad38)") (class "Default")
      (node (ref "U3") (pin "38") (pinfunction "IO2_38") (pintype "passive"))
    )
    (net (code "48") (name "unconnected-(U3-IO3-Pad15)") (class "Default")
      (node (ref "U3") (pin "15") (pinfunction "IO3_15") (pintype "passive"))
    )
    (net (code "49") (name "unconnected-(U3-IO4-Pad4)") (class "Default")
      (node (ref "U3") (pin "4") (pinfunction "IO4_4") (pintype "passive"))
    )
    (net (code "50") (name "unconnected-(U3-IO5-Pad5)") (class "Default")
      (node (ref "U3") (pin "5") (pinfunction "IO5_5") (pintype "passive"))
    )
    (net (code "51") (name "unconnected-(U3-IO6-Pad6)") (class "Default")
      (node (ref "U3") (pin "6") (pinfunction "IO6_6") (pintype "passive"))
    )
    (net (code "52") (name "unconnected-(U3-IO7-Pad7)") (class "Default")
      (node (ref "U3") (pin "7") (pinfunction "IO7_7") (pintype "passive"))
    )
    (net (code "53") (name "unconnected-(U3-IO8-Pad12)") (class "Default")
      (node (ref "U3") (pin "12") (pinfunction "IO8_12") (pintype "passive"))
    )
    (net (code "54") (name "unconnected-(U3-IO9-Pad17)") (class "Default")
      (node (ref "U3") (pin "17") (pinfunction "IO9_17") (pintype "passive"))
    )
    (net (code "55") (name "unconnected-(U3-IO10-Pad18)") (class "Default")
      (node (ref "U3") (pin "18") (pinfunction "IO10_18") (pintype "passive"))
    )
    (net (code "56") (name "unconnected-(U3-IO11-Pad19)") (class "Default")
      (node (ref "U3") (pin "19") (pinfunction "IO11_19") (pintype "passive"))
    )
    (net (code "57") (name "unconnected-(U3-IO12-Pad20)") (class "Default")
      (node (ref "U3") (pin "20") (pinfunction "IO12_20") (pintype "passive"))
    )
    (net (code "58") (name "unconnected-(U3-IO13-Pad21)") (class "Default")
      (node (ref "U3") (pin "21") (pinfunction "IO13_21") (pintype "passive"))
    )
    (net (code "59") (name "unconnected-(U3-IO14-Pad22)") (class "Default")
      (node (ref "U3") (pin "22") (pinfunction "IO14_22") (pintype "passive"))
    )
    (net (code "60") (name "unconnected-(U3-IO15-Pad8)") (class "Default")
      (node (ref "U3") (pin "8") (pinfunction "IO15_8") (pintype "passive"))
    )
    (net (code "61") (name "unconnected-(U3-IO16-Pad9)") (class "Default")
      (node (ref "U3") (pin "9") (pinfunction "IO16_9") (pintype "passive"))
    )
    (net (code "62") (name "unconnected-(U3-IO17-Pad10)") (class "Default")
      (node (ref "U3") (pin "10") (pinfunction "IO17_10") (pintype "passive"))
    )
    (net (code "63") (name "unconnected-(U3-IO18-Pad11)") (class "Default")
      (node (ref "U3") (pin "11") (pinfunction "IO18_11") (pintype "passive"))
    )
    (net (code "64") (name "unconnected-(U3-IO35-Pad28)") (class "Default")
      (node (ref "U3") (pin "28") (pinfunction "IO35_28") (pintype "passive"))
    )
    (net (code "65") (name "unconnected-(U3-IO36-Pad29)") (class "Default")
      (node (ref "U3") (pin "29") (pinfunction "IO36_29") (pintype "passive"))
    )
    (net (code "66") (name "unconnected-(U3-IO37-Pad30)") (class "Default")
      (node (ref "U3") (pin "30") (pinfunction "IO37_30") (pintype "passive"))
    )
    (net (code "67") (name "unconnected-(U3-IO39-Pad32)") (class "Default")
      (node (ref "U3") (pin "32") (pinfunction "IO39_32") (pintype "passive"))
    )
    (net (code "68") (name "unconnected-(U3-IO46-Pad16)") (class "Default")
      (node (ref "U3") (pin "16") (pinfunction "IO46_16") (pintype "passive"))
    )
    (net (code "69") (name "unconnected-(U6-N.C.-Pad5)") (class "Default")
      (node (ref "U6") (pin "5") (pinfunction "N.C._5") (pintype "passive+no_connect"))
    )
    (net (code "70") (name "unconnected-(U6-N.C.-Pad6)") (class "Default")
      (node (ref "U6") (pin "6") (pinfunction "N.C._6") (pintype "passive+no_connect"))
    )
    (net (code "71") (name "unconnected-(U6-N.C.-Pad12)") (class "Default")
      (node (ref "U6") (pin "12") (pinfunction "N.C._12") (pintype "passive+no_connect"))
    )
    (net (code "72") (name "unconnected-(U6-N.C.-Pad13)") (class "Default")
      (node (ref "U6") (pin "13") (pinfunction "N.C._13") (pintype "passive+no_connect"))
    )
    (net (code "73") (name "unconnected-(U7-N{slash}C-Pad2)") (class "Default")
      (node (ref "U7") (pin "2") (pinfunction "N/C_2") (pintype "passive+no_connect"))
    )
    (net (code "74") (name "unconnected-(U8-NC-Pad4)") (class "Default")
      (node (ref "U8") (pin "4") (pinfunction "NC_4") (pintype "passive+no_connect"))
    )
    (net (code "75") (name "unconnected-(U8-NC-Pad6)") (class "Default")
      (node (ref "U8") (pin "6") (pinfunction "NC_6") (pintype "passive+no_connect"))
    )
    (net (code "76") (name "unconnected-(USB1-RX1+-PadB11)") (class "Default")
      (node (ref "USB1") (pin "B11") (pinfunction "RX1+_B11") (pintype "passive"))
    )
    (net (code "77") (name "unconnected-(USB1-RX1--PadB10)") (class "Default")
      (node (ref "USB1") (pin "B10") (pinfunction "RX1-_B10") (pintype "passive"))
    )
    (net (code "78") (name "unconnected-(USB1-RX2+-PadA11)") (class "Default")
      (node (ref "USB1") (pin "A11") (pinfunction "RX2+_A11") (pintype "passive"))
    )
    (net (code "79") (name "unconnected-(USB1-RX2--PadA10)") (class "Default")
      (node (ref "USB1") (pin "A10") (pinfunction "RX2-_A10") (pintype "passive"))
    )
    (net (code "80") (name "unconnected-(USB1-SBU1-PadA8)") (class "Default")
      (node (ref "USB1") (pin "A8") (pinfunction "SBU1_A8") (pintype "passive"))
    )
    (net (code "81") (name "unconnected-(USB1-SBU2-PadB8)") (class "Default")
      (node (ref "USB1") (pin "B8") (pinfunction "SBU2_B8") (pintype "passive"))
    )
    (net (code "82") (name "unconnected-(USB1-TX1+-PadA2)") (class "Default")
      (node (ref "USB1") (pin "A2") (pinfunction "TX1+_A2") (pintype "passive"))
    )
    (net (code "83") (name "unconnected-(USB1-TX1--PadA3)") (class "Default")
      (node (ref "USB1") (pin "A3") (pinfunction "TX1-_A3") (pintype "passive"))
    )
    (net (code "84") (name "unconnected-(USB1-TX2+-PadB2)") (class "Default")
      (node (ref "USB1") (pin "B2") (pinfunction "TX2+_B2") (pintype "passive"))
    )
    (net (code "85") (name "unconnected-(USB1-TX2--PadB3)") (class "Default")
      (node (ref "USB1") (pin "B3") (pinfunction "TX2-_B3") (pintype "passive"))
    )
  )
)
